# SBH_Microcontroller.net
KiCad netlist of a schematic drawn in Altium Designer
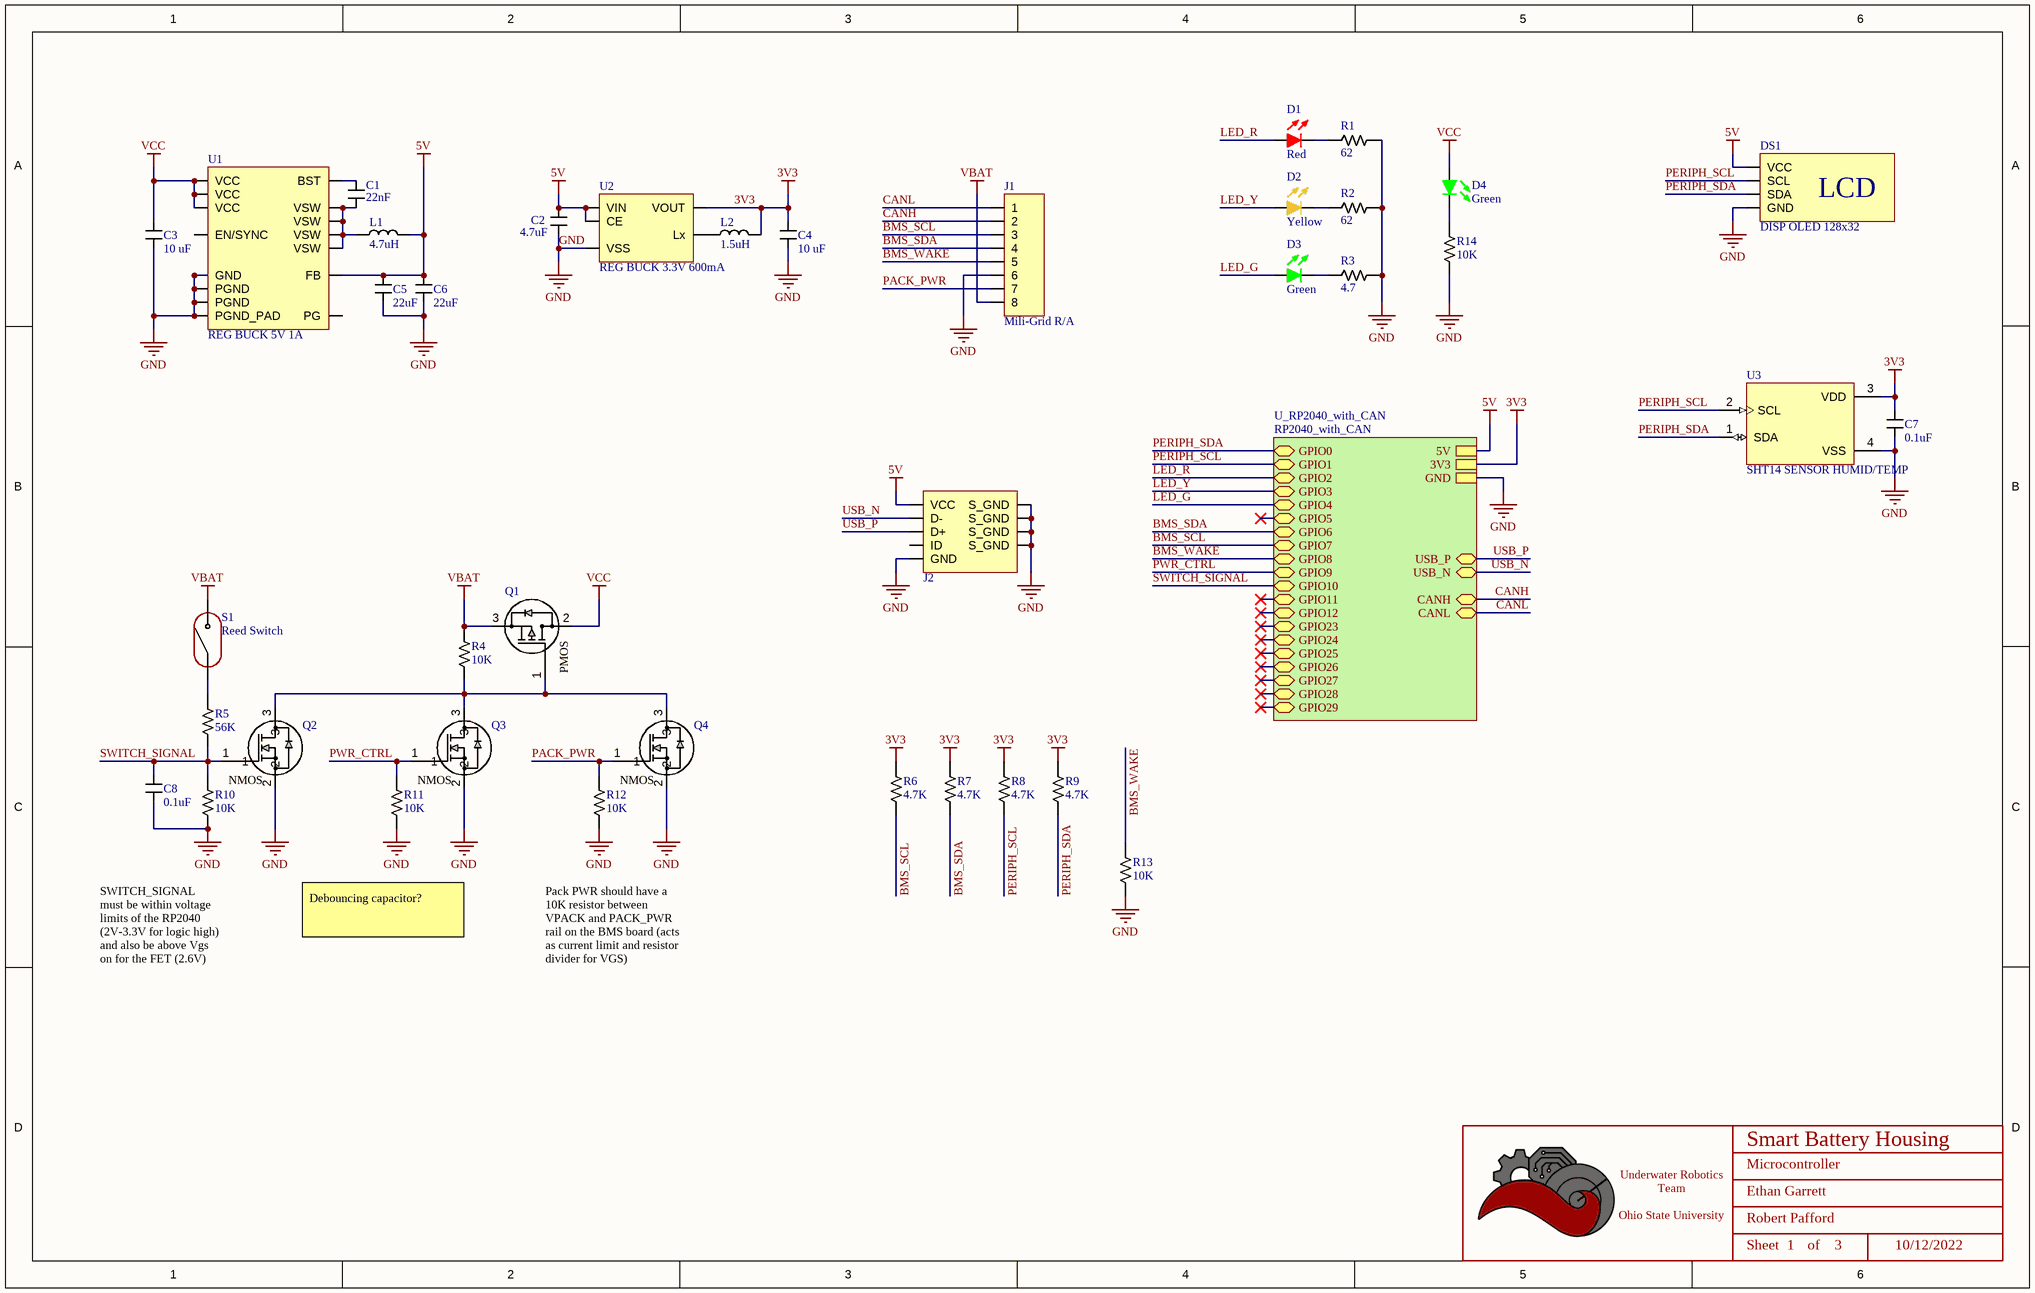
[diagram p0: SBH_Microcontroller.SchDoc]

(export (version "E")
  (design (tool "Eeschema 10.0.6"))
  (components
    (comp (ref "*")
      (value "Title_Block")
      (footprint "LOGO")
      (description "UWRT Schematic Title Block Template\r\n\r\nCreated June 2021, Dylan Trainor")
      (libsource (lib "UWRT") (part "Title_Block"))
    )
    (comp (ref "C1")
      (value "22nF")
      (footprint "CAPACITOR_0402")
      (description "Cap 22nF 25V +/-10%\r\nCeramic 0402")
      (fields
        (field (name "TOLERANCE") "+/- 10%")
        (field (name "VOLTAGE") "25V")
        (field (name "MADE BY") "Robert Pafford")
      )
      (libsource (lib "Capacitors") (part "CAPACITOR_0.022uF_0402"))
    )
    (comp (ref "C2")
      (value "4.7uF")
      (footprint "CAPACITOR_0603")
      (description "Cap 4.7uF 6.3V +/-10%\r\nCeramic 0603")
      (fields
        (field (name "TOLERANCE") "+/- 10%")
        (field (name "VOLTAGE") "6.3V")
        (field (name "MADE BY") "Robert Pafford")
      )
      (libsource (lib "Capacitors") (part "CAPACITOR_4.7uF_0603"))
    )
    (comp (ref "C3")
      (value "10uF Ceramic 25V")
      (footprint "CAPACITOR_1206")
      (description "Cap 10uF 25V +/-10%\r\nCeramic 1206")
      (fields
        (field (name "TOLERANCE") "+/- 10%")
        (field (name "VOLTAGE") "25V")
        (field (name "VALUE (UF)") "10 uF")
        (field (name "MADE BY") "Robert Pafford")
      )
      (libsource (lib "Capacitors") (part "CAPACITOR_10uF_1206"))
    )
    (comp (ref "C4")
      (value "10uF Ceramic 6.3V")
      (footprint "CAPACITOR_0603")
      (description "Cap 10uF 6.3V +/-20%\r\nCeramic 0603")
      (fields
        (field (name "TOLERANCE") "+/- 20%")
        (field (name "VOLTAGE") "6.3V")
        (field (name "VALUE (UF)") "10 uF")
        (field (name "MADE BY") "Flip B")
      )
      (libsource (lib "Capacitors") (part "CAPACITOR_10uF_0603"))
    )
    (comp (ref "C5")
      (value "22uF")
      (footprint "CAPACITOR_0805")
      (description "Cap 22uF 10V +/-20% X5R\r\nCeramic 0805")
      (fields
        (field (name "TOLERANCE") "+/- 20%")
        (field (name "VOLTAGE") "10V")
        (field (name "MADE BY") "Robert Pafford")
      )
      (libsource (lib "Capacitors") (part "CAPACITOR_22uF_0805"))
    )
    (comp (ref "C6")
      (value "22uF")
      (footprint "CAPACITOR_0805")
      (description "Cap 22uF 10V +/-20% X5R\r\nCeramic 0805")
      (fields
        (field (name "TOLERANCE") "+/- 20%")
        (field (name "VOLTAGE") "10V")
        (field (name "MADE BY") "Robert Pafford")
      )
      (libsource (lib "Capacitors") (part "CAPACITOR_22uF_0805"))
    )
    (comp (ref "C7")
      (value "0.1uF")
      (footprint "CAPACITOR_0402")
      (description "Cap 100nF 25V +/-10%\r\nCeramic 0402")
      (fields
        (field (name "TOLERANCE") "+/- 10%")
        (field (name "VOLTAGE") "25V")
        (field (name "MADE BY") "Robert Pafford")
      )
      (libsource (lib "Capacitors") (part "CAPACITOR_0.1uF_0402"))
    )
    (comp (ref "C8")
      (value "0.1uF")
      (footprint "CAPACITOR_0402")
      (description "Cap 100nF 25V +/-10%\r\nCeramic 0402")
      (fields
        (field (name "TOLERANCE") "+/- 10%")
        (field (name "VOLTAGE") "25V")
        (field (name "MADE BY") "Robert Pafford")
      )
      (libsource (lib "Capacitors") (part "CAPACITOR_0.1uF_0402"))
    )
    (comp (ref "D1")
      (value "150060RS75000")
      (footprint "LED_0603")
      (description "LED Red Vf= 2V If = 0.020A\r\n150060RS75000")
      (fields (field (name "COLOR") "Red") (field (name "MADE BY") "Robert Pafford"))
      (libsource (lib "Diodes") (part "LED_Red_0603"))
    )
    (comp (ref "D2")
      (value "150060YS75000")
      (footprint "LED_0603")
      (description "LED Yellow Vf= 2V If = 0.020A\r\n150060YS75000")
      (fields (field (name "COLOR") "Yellow") (field (name "MADE BY") "Robert Pafford"))
      (libsource (lib "Diodes") (part "LED_Yellow_0603"))
    )
    (comp (ref "D3")
      (value "150060GS75000")
      (footprint "LED_0603")
      (description "LED Green Vf= 3.2V If = 0.025A\r\n150060GS75000")
      (fields (field (name "COLOR") "Green") (field (name "MADE BY") "Flip B"))
      (libsource (lib "Diodes") (part "LED_Green_0603_3.2V"))
    )
    (comp (ref "D4")
      (value "150060GS75000")
      (footprint "LED_0603")
      (description "LED Green Vf= 3.2V If = 0.025A\r\n150060GS75000")
      (fields (field (name "COLOR") "Green") (field (name "MADE BY") "Flip B"))
      (libsource (lib "Diodes") (part "LED_Green_0603_3.2V"))
    )
    (comp (ref "DS1")
      (value "DISP OLED 128x32")
      (footprint "OLED_I2C_128x32")
      (description "0.91'' 128x32 I2C OLED LCD Display Module")
      (fields (field (name "MADE BY") "Robert Pafford"))
      (libsource (lib "Modules") (part "OLED_I2C_128x32"))
    )
    (comp (ref "J1")
      (value "Mili-Grid R/A")
      (footprint "Molex_Mili-Grid_2x4PIN_2.00MM_RA")
      (description "Molex Mili-Grid 2.00mm pitch 8 Pos Right Angle")
      (fields (field (name "MANUFACTURER") "Molex") (field (name "CREATED BY") "Flip B"))
      (libsource (lib "Connectors") (part "CONN_MOLEX_MiliGrid_8POS_R/A"))
    )
    (comp (ref "J2")
      (value "USB_MICRO R/A")
      (footprint "CONN_MINIUSB")
      (description "Amphenol Micro USB-B\r\nUSB2.0 5 Pin Right Angle SMD")
      (fields (field (name "MANUFACTURER") "Amphenol") (field (name "CREATED BY") "Flip B"))
      (libsource (lib "Connectors") (part "CONN_MICROUSB"))
    )
    (comp (ref "L1")
      (value "4.7uH")
      (footprint "INDUCTOR_SLF7045")
      (description "4.7 µH Shielded Drum Core, Wirewound Inductor 2.1 A 36mOhm Max Nonstandard")
      (fields
        (field (name "TOLERANCE") "+/- 20%")
        (field (name "Comment") "4.7uH Shielded Drum Core")
        (field (name "MADE BY") "Robert Pafford")
      )
      (libsource (lib "Inductors") (part "INDUCTOR_4.7uH_SLF7045T"))
    )
    (comp (ref "L2")
      (value "1.5uH")
      (footprint "INDUCTOR_NR3015")
      (description "Inductor Shielded 1.5uH 1.8A +/-30%")
      (fields
        (field (name "TOLERANCE") "+/- 30%")
        (field (name "Comment") "1.5uH Shielded")
        (field (name "MADE BY") "Robert Pafford")
      )
      (libsource (lib "Inductors") (part "INDUCTOR_1.5uH_NR3015"))
    )
    (comp (ref "Q1")
      (value "DMP3056L-7")
      (footprint "SOT-23-3")
      (description "P-Channel 30V 4.3A (Ta) 1.38W (Ta) Surface Mount SOT23")
      (fields (field (name "CREATED BY") "John Ulm") (field (name "REVIEWED BY") "---"))
      (libsource (lib "Transistors") (part "DMP3056L-7"))
    )
    (comp (ref "Q2")
      (value "MOSFET N-CH 30V 5.8A SOT-23-3")
      (footprint "SOT-23-3")
      (description "N-Channel 30 V 5.8A (Ta) 1.4W (Ta) Surface Mount SOT-23-3")
      (fields (field (name "MANUFACTURER _PART_NUMBER") "AO3404A") (field (name "CREATED BY") "Dylan T"))
      (libsource (lib "Transistors") (part "AO3404A"))
    )
    (comp (ref "Q3")
      (value "MOSFET N-CH 30V 5.8A SOT-23-3")
      (footprint "SOT-23-3")
      (description "N-Channel 30 V 5.8A (Ta) 1.4W (Ta) Surface Mount SOT-23-3")
      (fields (field (name "MANUFACTURER _PART_NUMBER") "AO3404A") (field (name "CREATED BY") "Dylan T"))
      (libsource (lib "Transistors") (part "AO3404A"))
    )
    (comp (ref "Q4")
      (value "MOSFET N-CH 30V 5.8A SOT-23-3")
      (footprint "SOT-23-3")
      (description "N-Channel 30 V 5.8A (Ta) 1.4W (Ta) Surface Mount SOT-23-3")
      (fields (field (name "MANUFACTURER _PART_NUMBER") "AO3404A") (field (name "CREATED BY") "Dylan T"))
      (libsource (lib "Transistors") (part "AO3404A"))
    )
    (comp (ref "R1")
      (value "62 Ohm 1% 1/4W")
      (footprint "RESISTOR_0603")
      (description "RES SMD 62 OHM 1% 1/4W 0603")
      (fields
        (field (name "TOLERANCE") "+/- 1%")
        (field (name "VALUE  (OHMS)") "62")
        (field (name "MADE BY") "Robert Pafford")
      )
      (libsource (lib "Resistors") (part "RESISTOR_62_0603"))
    )
    (comp (ref "R2")
      (value "62 Ohm 1% 1/4W")
      (footprint "RESISTOR_0603")
      (description "RES SMD 62 OHM 1% 1/4W 0603")
      (fields
        (field (name "TOLERANCE") "+/- 1%")
        (field (name "VALUE  (OHMS)") "62")
        (field (name "MADE BY") "Robert Pafford")
      )
      (libsource (lib "Resistors") (part "RESISTOR_62_0603"))
    )
    (comp (ref "R3")
      (value "4.7 Ohm 5% 1/8W")
      (footprint "RESISTOR_0603")
      (description "RES 4.7 OHM 5% 1/8W 0603")
      (fields
        (field (name "TOLERANCE") "+/- 5%")
        (field (name "VALUE  (OHMS)") "4.7")
        (field (name "MADE BY") "Robert Pafford")
      )
      (libsource (lib "Resistors") (part "RESISTOR_4.7_0603"))
    )
    (comp (ref "R4")
      (value "10k Ohm 5% 1/10W")
      (footprint "RESISTOR_0603")
      (description "RES 10k OHM 5% 1/10W 0603")
      (fields
        (field (name "TOLERANCE") "+/- 5%")
        (field (name "VALUE  (OHMS)") "10K")
        (field (name "MADE BY") "Robert Pafford")
      )
      (libsource (lib "Resistors") (part "RESISTOR_10K_0603"))
    )
    (comp (ref "R5")
      (value "56k Ohm 1% 1/16W")
      (footprint "RESISTOR_0402")
      (description "RES 56k OHM 1% 1/16W 0402")
      (fields
        (field (name "TOLERANCE") "+/- 1%")
        (field (name "VALUE  (OHMS)") "56K")
        (field (name "MADE BY") "Robert Pafford")
      )
      (libsource (lib "Resistors") (part "RESISTOR_56K_0402"))
    )
    (comp (ref "R6")
      (value "4.7k Ohm 5% 1/10W")
      (footprint "RESISTOR_0603")
      (description "RES 4.7k OHM 5% 1/10W 0603")
      (fields
        (field (name "TOLERANCE") "+/- 5%")
        (field (name "VALUE  (OHMS)") "4.7K")
        (field (name "MADE BY") "Robert Pafford")
      )
      (libsource (lib "Resistors") (part "RESISTOR_4.7K_0603"))
    )
    (comp (ref "R7")
      (value "4.7k Ohm 5% 1/10W")
      (footprint "RESISTOR_0603")
      (description "RES 4.7k OHM 5% 1/10W 0603")
      (fields
        (field (name "TOLERANCE") "+/- 5%")
        (field (name "VALUE  (OHMS)") "4.7K")
        (field (name "MADE BY") "Robert Pafford")
      )
      (libsource (lib "Resistors") (part "RESISTOR_4.7K_0603"))
    )
    (comp (ref "R8")
      (value "4.7k Ohm 5% 1/10W")
      (footprint "RESISTOR_0603")
      (description "RES 4.7k OHM 5% 1/10W 0603")
      (fields
        (field (name "TOLERANCE") "+/- 5%")
        (field (name "VALUE  (OHMS)") "4.7K")
        (field (name "MADE BY") "Robert Pafford")
      )
      (libsource (lib "Resistors") (part "RESISTOR_4.7K_0603"))
    )
    (comp (ref "R9")
      (value "4.7k Ohm 5% 1/10W")
      (footprint "RESISTOR_0603")
      (description "RES 4.7k OHM 5% 1/10W 0603")
      (fields
        (field (name "TOLERANCE") "+/- 5%")
        (field (name "VALUE  (OHMS)") "4.7K")
        (field (name "MADE BY") "Robert Pafford")
      )
      (libsource (lib "Resistors") (part "RESISTOR_4.7K_0603"))
    )
    (comp (ref "R10")
      (value "10k Ohm 5% 1/10W")
      (footprint "RESISTOR_0603")
      (description "RES 10k OHM 5% 1/10W 0603")
      (fields
        (field (name "TOLERANCE") "+/- 5%")
        (field (name "VALUE  (OHMS)") "10K")
        (field (name "MADE BY") "Robert Pafford")
      )
      (libsource (lib "Resistors") (part "RESISTOR_10K_0603"))
    )
    (comp (ref "R11")
      (value "10k Ohm 5% 1/10W")
      (footprint "RESISTOR_0603")
      (description "RES 10k OHM 5% 1/10W 0603")
      (fields
        (field (name "TOLERANCE") "+/- 5%")
        (field (name "VALUE  (OHMS)") "10K")
        (field (name "MADE BY") "Robert Pafford")
      )
      (libsource (lib "Resistors") (part "RESISTOR_10K_0603"))
    )
    (comp (ref "R12")
      (value "10k Ohm 5% 1/10W")
      (footprint "RESISTOR_0603")
      (description "RES 10k OHM 5% 1/10W 0603")
      (fields
        (field (name "TOLERANCE") "+/- 5%")
        (field (name "VALUE  (OHMS)") "10K")
        (field (name "MADE BY") "Robert Pafford")
      )
      (libsource (lib "Resistors") (part "RESISTOR_10K_0603"))
    )
    (comp (ref "R13")
      (value "10k Ohm 5% 1/10W")
      (footprint "RESISTOR_0603")
      (description "RES 10k OHM 5% 1/10W 0603")
      (fields
        (field (name "TOLERANCE") "+/- 5%")
        (field (name "VALUE  (OHMS)") "10K")
        (field (name "MADE BY") "Robert Pafford")
      )
      (libsource (lib "Resistors") (part "RESISTOR_10K_0603"))
    )
    (comp (ref "R14")
      (value "10k Ohm 5% 1/10W")
      (footprint "RESISTOR_0603")
      (description "RES 10k OHM 5% 1/10W 0603")
      (fields
        (field (name "TOLERANCE") "+/- 5%")
        (field (name "VALUE  (OHMS)") "10K")
        (field (name "MADE BY") "Robert Pafford")
      )
      (libsource (lib "Resistors") (part "RESISTOR_10K_0603"))
    )
    (comp (ref "S1")
      (value "Reed Switch")
      (footprint "MDSR-7")
      (fields (field (name "MADE BY") "Robert Pafford"))
      (libsource (lib "Switches") (part "Reed Switch"))
    )
    (comp (ref "U1")
      (value "REG BUCK 5V 1A")
      (footprint "QFN-16 (3x3)")
      (description "Buck Switching Regulator IC Positive Fixed 5V 1 Output 1A 16-VFQFN Exposed Pad")
      (fields (field (name "MADE BY") "Robert Pafford"))
      (libsource (lib "Integrated Circuits") (part "TS30041-M050QFNR"))
    )
    (comp (ref "U2")
      (value "REG BUCK 3.3V 600mA")
      (footprint "SOT-23-5")
      (description "Buck Switching Regulator IC Positive Fixed 3.3V 1 Output 600mA SOT25")
      (fields (field (name "MADE BY") "Robert Pafford"))
      (libsource (lib "Integrated Circuits") (part "XC9236A33DMR-G"))
    )
    (comp (ref "U3")
      (value "SHT14 SENSOR HUMID/TEMP")
      (footprint "XDCR_SHT41-AD1B-R2")
      (description "Digital Relative Humidity Temperature Sensor, Â±1.8 / max 2.5 %RH, Â±0.2 Â°C, Ultra-Low-Power")
      (fields (field (name "MP") "SHT41-AD1B-R2") (field (name "MF") "Sensirion"))
      (libsource (lib "Integrated Circuits") (part "SHT41-AD1B-R2"))
    )
  )
  (nets
    (net (code "1") (name "/BMS_SCL") (class "Default")
      (node (ref "J1") (pin "3") (pinfunction "3_3") (pintype "passive"))
      (node (ref "R6") (pin "2") (pinfunction "2_2") (pintype "passive"))
    )
    (net (code "2") (name "/BMS_SDA") (class "Default")
      (node (ref "J1") (pin "4") (pinfunction "4_4") (pintype "passive"))
      (node (ref "R7") (pin "2") (pinfunction "2_2") (pintype "passive"))
    )
    (net (code "3") (name "/BMS_WAKE") (class "Default")
      (node (ref "J1") (pin "5") (pinfunction "5_5") (pintype "passive"))
      (node (ref "R13") (pin "1") (pinfunction "1_1") (pintype "passive"))
    )
    (net (code "4") (name "/CANH") (class "Default")
      (node (ref "J1") (pin "2") (pinfunction "2_2") (pintype "passive"))
    )
    (net (code "5") (name "/CANL") (class "Default")
      (node (ref "J1") (pin "1") (pinfunction "1_1") (pintype "passive"))
    )
    (net (code "16") (name "/LED_G") (class "Default")
      (node (ref "D3") (pin "1") (pinfunction "1_1") (pintype "passive"))
    )
    (net (code "17") (name "/LED_R") (class "Default")
      (node (ref "D1") (pin "1") (pinfunction "1_1") (pintype "passive"))
    )
    (net (code "18") (name "/LED_Y") (class "Default")
      (node (ref "D2") (pin "1") (pinfunction "1_1") (pintype "passive"))
    )
    (net (code "19") (name "/PACK_PWR") (class "Default")
      (node (ref "J1") (pin "7") (pinfunction "7_7") (pintype "passive"))
      (node (ref "Q4") (pin "1") (pinfunction "1_1") (pintype "passive"))
      (node (ref "R12") (pin "1") (pinfunction "1_1") (pintype "passive"))
    )
    (net (code "20") (name "/PERIPH_SCL") (class "Default")
      (node (ref "DS1") (pin "3") (pinfunction "SCL_3") (pintype "passive"))
      (node (ref "R8") (pin "2") (pinfunction "2_2") (pintype "passive"))
      (node (ref "U3") (pin "2") (pinfunction "SCL_2") (pintype "input"))
    )
    (net (code "21") (name "/PERIPH_SDA") (class "Default")
      (node (ref "DS1") (pin "4") (pinfunction "SDA_4") (pintype "passive"))
      (node (ref "R9") (pin "2") (pinfunction "2_2") (pintype "passive"))
      (node (ref "U3") (pin "1") (pinfunction "SDA_1") (pintype "bidirectional"))
    )
    (net (code "22") (name "/PWR_CTRL") (class "Default")
      (node (ref "Q3") (pin "1") (pinfunction "1_1") (pintype "passive"))
      (node (ref "R11") (pin "1") (pinfunction "1_1") (pintype "passive"))
    )
    (net (code "23") (name "/SWITCH_SIGNAL") (class "Default")
      (node (ref "C8") (pin "1") (pinfunction "1_1") (pintype "passive"))
      (node (ref "Q2") (pin "1") (pinfunction "1_1") (pintype "passive"))
      (node (ref "R10") (pin "1") (pinfunction "1_1") (pintype "passive"))
      (node (ref "R5") (pin "2") (pinfunction "2_2") (pintype "passive"))
    )
    (net (code "24") (name "/USB_N") (class "Default")
      (node (ref "J2") (pin "2") (pinfunction "D-_2") (pintype "passive"))
    )
    (net (code "25") (name "/USB_P") (class "Default")
      (node (ref "J2") (pin "3") (pinfunction "D+_3") (pintype "passive"))
    )
    (net (code "26") (name "3V3") (class "Default")
      (node (ref "C4") (pin "1") (pinfunction "1_1") (pintype "passive"))
      (node (ref "C7") (pin "1") (pinfunction "1_1") (pintype "passive"))
      (node (ref "L2") (pin "1") (pinfunction "1_1") (pintype "passive"))
      (node (ref "R6") (pin "1") (pinfunction "1_1") (pintype "passive"))
      (node (ref "R7") (pin "1") (pinfunction "1_1") (pintype "passive"))
      (node (ref "R8") (pin "1") (pinfunction "1_1") (pintype "passive"))
      (node (ref "R9") (pin "1") (pinfunction "1_1") (pintype "passive"))
      (node (ref "U2") (pin "4") (pinfunction "VOUT_4") (pintype "passive"))
      (node (ref "U3") (pin "3") (pinfunction "VDD_3") (pintype "power_in"))
    )
    (net (code "27") (name "5V") (class "Default")
      (node (ref "C2") (pin "1") (pinfunction "1_1") (pintype "passive"))
      (node (ref "C5") (pin "1") (pinfunction "1_1") (pintype "passive"))
      (node (ref "C6") (pin "1") (pinfunction "1_1") (pintype "passive"))
      (node (ref "DS1") (pin "2") (pinfunction "VCC_2") (pintype "passive"))
      (node (ref "J2") (pin "1") (pinfunction "VCC_1") (pintype "passive"))
      (node (ref "L1") (pin "1") (pinfunction "1_1") (pintype "passive"))
      (node (ref "U1") (pin "5") (pinfunction "FB_5") (pintype "passive"))
      (node (ref "U2") (pin "1") (pinfunction "VIN_1") (pintype "passive"))
      (node (ref "U2") (pin "3") (pinfunction "CE_3") (pintype "passive"))
    )
    (net (code "28") (name "GND") (class "Default")
      (node (ref "C2") (pin "2") (pinfunction "2_2") (pintype "passive"))
      (node (ref "C3") (pin "2") (pinfunction "2_2") (pintype "passive"))
      (node (ref "C4") (pin "2") (pinfunction "2_2") (pintype "passive"))
      (node (ref "C5") (pin "2") (pinfunction "2_2") (pintype "passive"))
      (node (ref "C6") (pin "2") (pinfunction "2_2") (pintype "passive"))
      (node (ref "C7") (pin "2") (pinfunction "2_2") (pintype "passive"))
      (node (ref "C8") (pin "2") (pinfunction "2_2") (pintype "passive"))
      (node (ref "DS1") (pin "1") (pinfunction "GND_1") (pintype "passive"))
      (node (ref "J1") (pin "6") (pinfunction "6_6") (pintype "passive"))
      (node (ref "J2") (pin "5") (pinfunction "GND_5") (pintype "passive"))
      (node (ref "J2") (pin "6") (pinfunction "S_GND_6") (pintype "passive"))
      (node (ref "J2") (pin "7") (pinfunction "S_GND_7") (pintype "passive"))
      (node (ref "J2") (pin "8") (pinfunction "S_GND_8") (pintype "passive"))
      (node (ref "J2") (pin "9") (pinfunction "S_GND_9") (pintype "passive"))
      (node (ref "Q2") (pin "2") (pinfunction "2_2") (pintype "passive"))
      (node (ref "Q3") (pin "2") (pinfunction "2_2") (pintype "passive"))
      (node (ref "Q4") (pin "2") (pinfunction "2_2") (pintype "passive"))
      (node (ref "R1") (pin "1") (pinfunction "1_1") (pintype "passive"))
      (node (ref "R10") (pin "2") (pinfunction "2_2") (pintype "passive"))
      (node (ref "R11") (pin "2") (pinfunction "2_2") (pintype "passive"))
      (node (ref "R12") (pin "2") (pinfunction "2_2") (pintype "passive"))
      (node (ref "R13") (pin "2") (pinfunction "2_2") (pintype "passive"))
      (node (ref "R14") (pin "2") (pinfunction "2_2") (pintype "passive"))
      (node (ref "R2") (pin "1") (pinfunction "1_1") (pintype "passive"))
      (node (ref "R3") (pin "1") (pinfunction "1_1") (pintype "passive"))
      (node (ref "U1") (pin "14") (pinfunction "PGND_14") (pintype "power_in"))
      (node (ref "U1") (pin "15") (pinfunction "PGND_15") (pintype "power_in"))
      (node (ref "U1") (pin "17") (pinfunction "PGND_PAD_17") (pintype "power_in"))
      (node (ref "U1") (pin "4") (pinfunction "GND_4") (pintype "power_in"))
      (node (ref "U2") (pin "2") (pinfunction "VSS_2") (pintype "passive"))
      (node (ref "U3") (pin "4") (pinfunction "VSS_4") (pintype "power_in"))
    )
    (net (code "29") (name "Net-(C1-Pad2)") (class "Default")
      (node (ref "C1") (pin "2") (pinfunction "2_2") (pintype "passive"))
      (node (ref "L1") (pin "2") (pinfunction "2_2") (pintype "passive"))
      (node (ref "U1") (pin "1") (pinfunction "VSW_1") (pintype "power_in"))
      (node (ref "U1") (pin "12") (pinfunction "VSW_12") (pintype "power_in"))
      (node (ref "U1") (pin "13") (pinfunction "VSW_13") (pintype "power_in"))
      (node (ref "U1") (pin "16") (pinfunction "VSW_16") (pintype "passive"))
    )
    (net (code "30") (name "Net-(D1-Pad2)") (class "Default")
      (node (ref "D1") (pin "2") (pinfunction "2_2") (pintype "passive"))
      (node (ref "R1") (pin "2") (pinfunction "2_2") (pintype "passive"))
    )
    (net (code "31") (name "Net-(D2-Pad2)") (class "Default")
      (node (ref "D2") (pin "2") (pinfunction "2_2") (pintype "passive"))
      (node (ref "R2") (pin "2") (pinfunction "2_2") (pintype "passive"))
    )
    (net (code "32") (name "Net-(D3-Pad2)") (class "Default")
      (node (ref "D3") (pin "2") (pinfunction "2_2") (pintype "passive"))
      (node (ref "R3") (pin "2") (pinfunction "2_2") (pintype "passive"))
    )
    (net (code "33") (name "Net-(D4-Pad2)") (class "Default")
      (node (ref "D4") (pin "2") (pinfunction "2_2") (pintype "passive"))
      (node (ref "R14") (pin "1") (pinfunction "1_1") (pintype "passive"))
    )
    (net (code "34") (name "Net-(Q1-Pad1)") (class "Default")
      (node (ref "Q1") (pin "1") (pinfunction "1_1") (pintype "passive"))
      (node (ref "Q2") (pin "3") (pinfunction "3_3") (pintype "passive"))
      (node (ref "Q3") (pin "3") (pinfunction "3_3") (pintype "passive"))
      (node (ref "Q4") (pin "3") (pinfunction "3_3") (pintype "passive"))
      (node (ref "R4") (pin "2") (pinfunction "2_2") (pintype "passive"))
    )
    (net (code "35") (name "Net-(R5-Pad1)") (class "Default")
      (node (ref "R5") (pin "1") (pinfunction "1_1") (pintype "passive"))
      (node (ref "S1") (pin "1") (pintype "passive"))
    )
    (net (code "36") (name "Net-(U1-BST)") (class "Default")
      (node (ref "C1") (pin "1") (pinfunction "1_1") (pintype "passive"))
      (node (ref "U1") (pin "10") (pinfunction "BST_10") (pintype "passive"))
    )
    (net (code "37") (name "Net-(U2-Lx)") (class "Default")
      (node (ref "L2") (pin "2") (pinfunction "2_2") (pintype "passive"))
      (node (ref "U2") (pin "5") (pinfunction "Lx_5") (pintype "passive"))
    )
    (net (code "38") (name "VBAT") (class "Default")
      (node (ref "J1") (pin "8") (pinfunction "8_8") (pintype "passive"))
      (node (ref "Q1") (pin "3") (pinfunction "3_3") (pintype "passive"))
      (node (ref "R4") (pin "1") (pinfunction "1_1") (pintype "passive"))
      (node (ref "S1") (pin "2") (pintype "passive"))
    )
    (net (code "39") (name "VCC") (class "Default")
      (node (ref "C3") (pin "1") (pinfunction "1_1") (pintype "passive"))
      (node (ref "D4") (pin "1") (pinfunction "1_1") (pintype "passive"))
      (node (ref "Q1") (pin "2") (pinfunction "2_2") (pintype "passive"))
      (node (ref "U1") (pin "11") (pinfunction "VCC_11") (pintype "power_in"))
      (node (ref "U1") (pin "2") (pinfunction "VCC_2") (pintype "power_in"))
      (node (ref "U1") (pin "3") (pinfunction "VCC_3") (pintype "power_in"))
    )
    (net (code "40") (name "unconnected-(J2-ID-Pad4)") (class "Default")
      (node (ref "J2") (pin "4") (pinfunction "ID_4") (pintype "passive"))
    )
    (net (code "41") (name "unconnected-(U1-EN{slash}SYNC-Pad9)") (class "Default")
      (node (ref "U1") (pin "9") (pinfunction "EN/SYNC_9") (pintype "passive"))
    )
    (net (code "42") (name "unconnected-(U1-PG-Pad8)") (class "Default")
      (node (ref "U1") (pin "8") (pinfunction "PG_8") (pintype "passive"))
    )
  )
)
